# UCSD_QuadCopter_Rev1.net
KiCad netlist of a schematic drawn in EAGLE
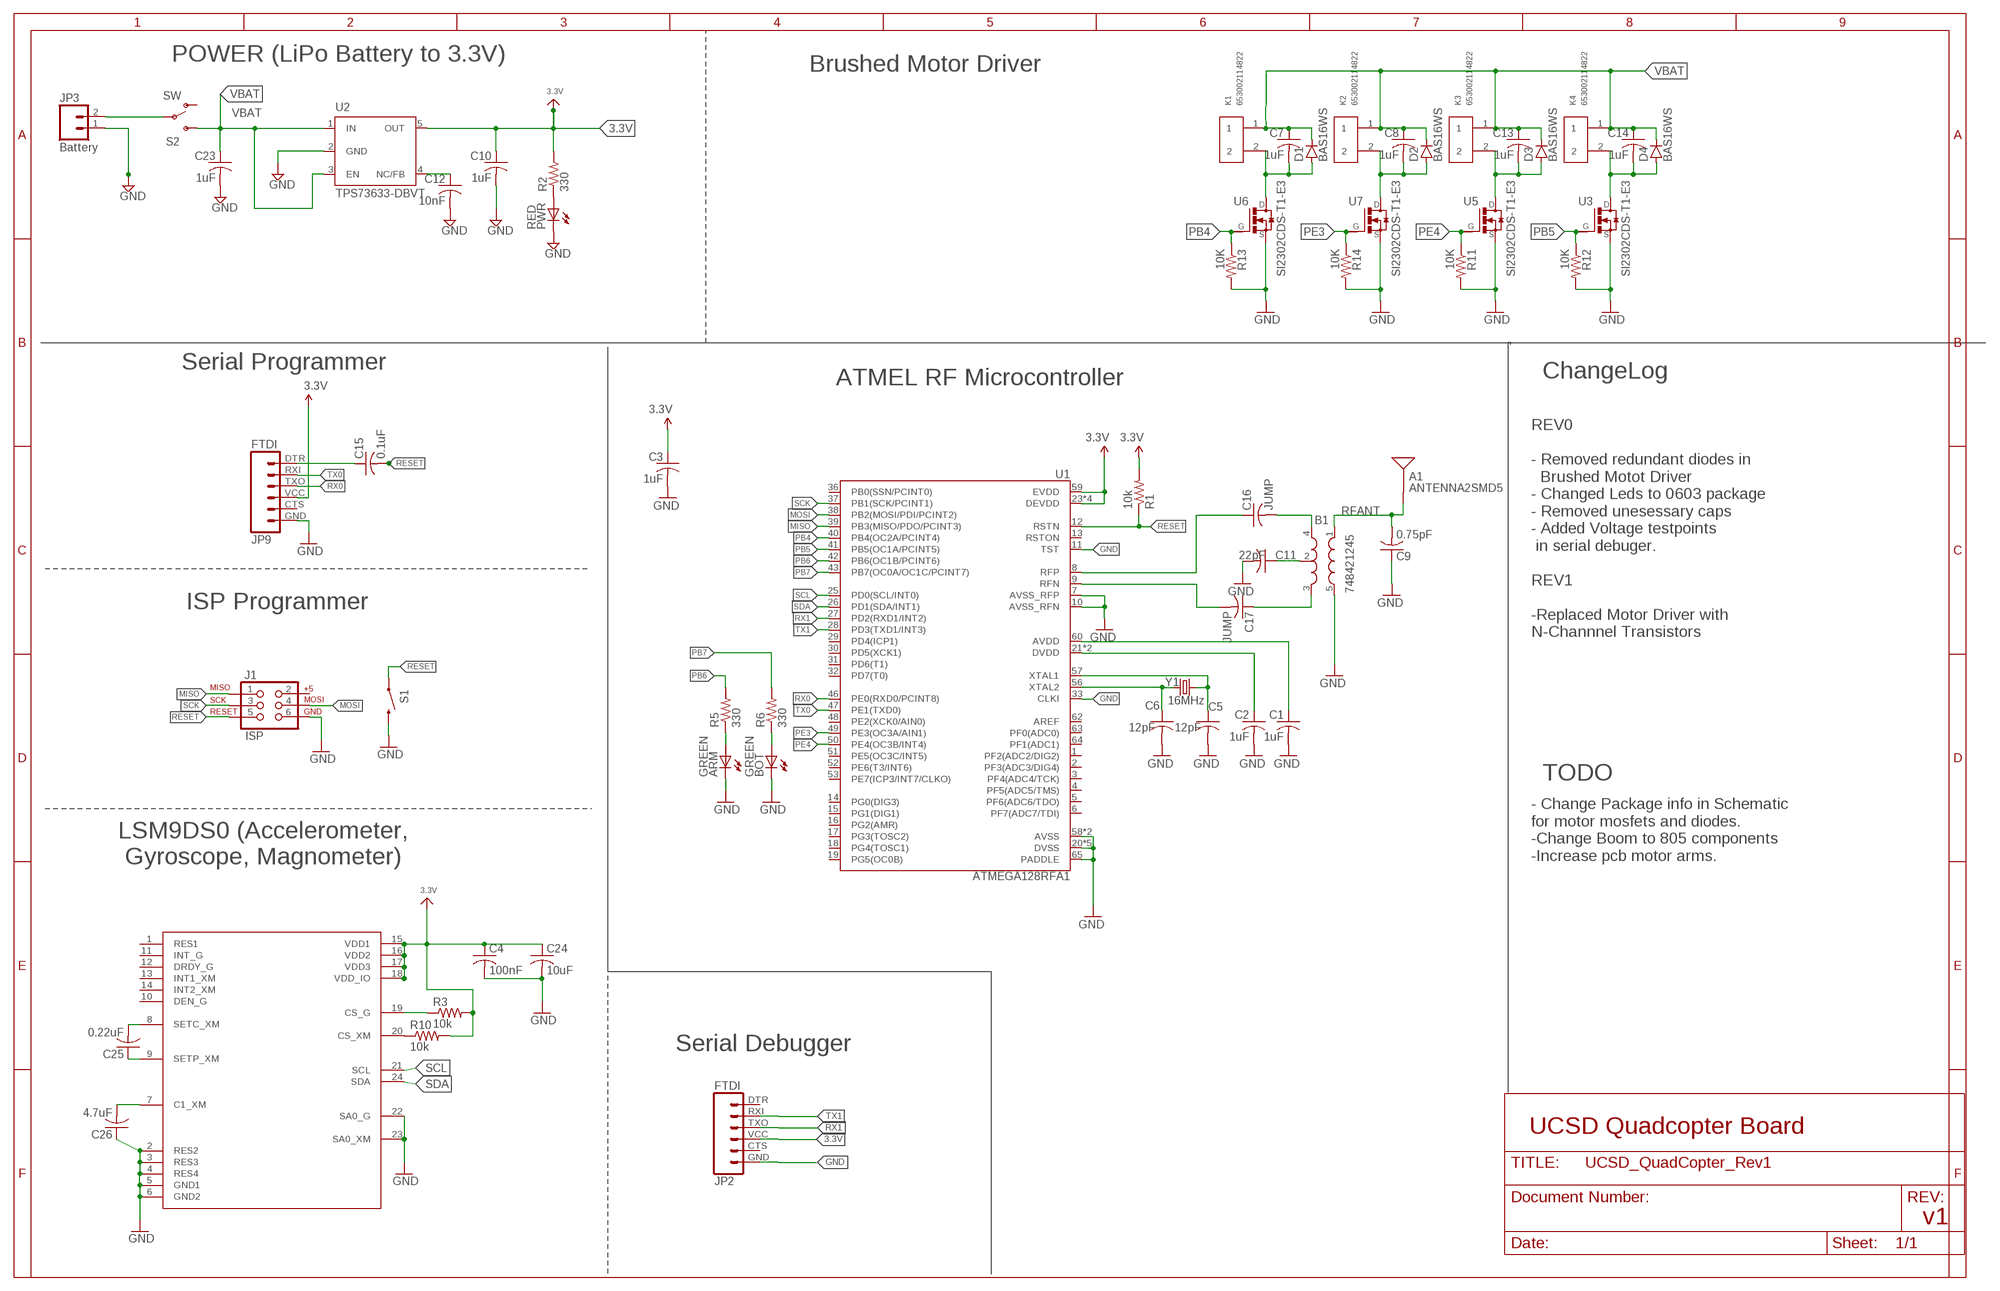
[diagram p0: schematic, sheet 1]

(export (version "E")
  (design (tool "Eeschema 10.0.6"))
  (components
    (comp (ref "A1")
      (value "ANTENNA2SMD5")
      (footprint "eagle-import:ANTENNA-CHIP5")
      (libsource (lib "eagle-import") (part "ANTENNA2SMD5"))
    )
    (comp (ref "ARM")
      (value "GREEN")
      (footprint "eagle-import:CHIP-LED0805")
      (libsource (lib "eagle-import") (part "LEDCHIP-LED0805"))
    )
    (comp (ref "B1")
      (value "748421245")
      (footprint "eagle-import:BALUN")
      (libsource (lib "eagle-import") (part "BALUN0805"))
    )
    (comp (ref "BOT")
      (value "GREEN")
      (footprint "eagle-import:CHIP-LED0805")
      (libsource (lib "eagle-import") (part "LEDCHIP-LED0805"))
    )
    (comp (ref "C1")
      (value "1uF")
      (footprint "eagle-import:C0805")
      (libsource (lib "eagle-import") (part "resistor_C-USC0805"))
    )
    (comp (ref "C2")
      (value "1uF")
      (footprint "eagle-import:C0805")
      (libsource (lib "eagle-import") (part "resistor_C-USC0805"))
    )
    (comp (ref "C3")
      (value "1uF")
      (footprint "eagle-import:C0805")
      (libsource (lib "eagle-import") (part "resistor_C-USC0805"))
    )
    (comp (ref "C4")
      (value "100nF")
      (footprint "eagle-import:C0805")
      (libsource (lib "eagle-import") (part "C-USC0805"))
    )
    (comp (ref "C5")
      (value "12pF")
      (footprint "eagle-import:C0805")
      (libsource (lib "eagle-import") (part "resistor_C-USC0805"))
    )
    (comp (ref "C6")
      (value "12pF")
      (footprint "eagle-import:C0805")
      (libsource (lib "eagle-import") (part "resistor_C-USC0805"))
    )
    (comp (ref "C7")
      (value "1uF")
      (footprint "eagle-import:C0805")
      (libsource (lib "eagle-import") (part "resistor_C-USC0805"))
    )
    (comp (ref "C8")
      (value "1uF")
      (footprint "eagle-import:C0805")
      (libsource (lib "eagle-import") (part "resistor_C-USC0805"))
    )
    (comp (ref "C9")
      (value "0.75pF")
      (footprint "eagle-import:C0805")
      (libsource (lib "eagle-import") (part "resistor_C-USC0805"))
    )
    (comp (ref "C10")
      (value "1uF")
      (footprint "eagle-import:C0805")
      (libsource (lib "eagle-import") (part "resistor_C-USC0805"))
    )
    (comp (ref "C11")
      (value "22pF")
      (footprint "eagle-import:C0805")
      (libsource (lib "eagle-import") (part "resistor_C-USC0805"))
    )
    (comp (ref "C12")
      (value "10nF")
      (footprint "eagle-import:C0805")
      (libsource (lib "eagle-import") (part "resistor_C-USC0805"))
    )
    (comp (ref "C13")
      (value "1uF")
      (footprint "eagle-import:C0805")
      (libsource (lib "eagle-import") (part "resistor_C-USC0805"))
    )
    (comp (ref "C14")
      (value "1uF")
      (footprint "eagle-import:C0805")
      (libsource (lib "eagle-import") (part "resistor_C-USC0805"))
    )
    (comp (ref "C15")
      (value "0.1uF")
      (footprint "eagle-import:C0805")
      (libsource (lib "eagle-import") (part "resistor_C-USC0805"))
    )
    (comp (ref "C16")
      (value "JUMP")
      (footprint "eagle-import:C0805")
      (libsource (lib "eagle-import") (part "resistor_C-USC0805"))
    )
    (comp (ref "C17")
      (value "JUMP")
      (footprint "eagle-import:C0805")
      (libsource (lib "eagle-import") (part "resistor_C-USC0805"))
    )
    (comp (ref "C23")
      (value "1uF")
      (footprint "eagle-import:C0805")
      (libsource (lib "eagle-import") (part "resistor_C-USC0805"))
    )
    (comp (ref "C24")
      (value "10uF")
      (footprint "eagle-import:C0805")
      (libsource (lib "eagle-import") (part "C-USC0805"))
    )
    (comp (ref "C25")
      (value "0.22uF")
      (footprint "eagle-import:C0805")
      (libsource (lib "eagle-import") (part "C-USC0805"))
    )
    (comp (ref "C26")
      (value "4.7uF")
      (footprint "eagle-import:C0805")
      (libsource (lib "eagle-import") (part "C-USC0805"))
    )
    (comp (ref "D1")
      (value "BAS16WS")
      (footprint "eagle-import:SOD323_ST")
      (libsource (lib "eagle-import") (part "BAS16WS"))
    )
    (comp (ref "D2")
      (value "BAS16WS")
      (footprint "eagle-import:SOD323_ST")
      (libsource (lib "eagle-import") (part "BAS16WS"))
    )
    (comp (ref "D3")
      (value "BAS16WS")
      (footprint "eagle-import:SOD323_ST")
      (libsource (lib "eagle-import") (part "BAS16WS"))
    )
    (comp (ref "D4")
      (value "BAS16WS")
      (footprint "eagle-import:SOD323_ST")
      (libsource (lib "eagle-import") (part "BAS16WS"))
    )
    (comp (ref "J1")
      (value "ISP")
      (footprint "eagle-import:2X3-NS")
      (libsource (lib "eagle-import") (part "AVR_SPI_PRG_6NS"))
    )
    (comp (ref "JP2")
      (value "FTDI")
      (footprint "eagle-import:FTDI_BASIC")
      (libsource (lib "eagle-import") (part "FTDI_BASICPTH"))
    )
    (comp (ref "JP3")
      (value "Battery")
      (footprint "eagle-import:1X02")
      (libsource (lib "eagle-import") (part "M02PTH"))
    )
    (comp (ref "JP9")
      (value "FTDI")
      (footprint "eagle-import:FTDI_BASIC")
      (libsource (lib "eagle-import") (part "FTDI_BASICPTH"))
    )
    (comp (ref "K1")
      (value "653002114822")
      (footprint "eagle-import:653002114822")
      (libsource (lib "eagle-import") (part "653002114822"))
    )
    (comp (ref "K2")
      (value "653002114822")
      (footprint "eagle-import:653002114822")
      (libsource (lib "eagle-import") (part "653002114822"))
    )
    (comp (ref "K3")
      (value "653002114822")
      (footprint "eagle-import:653002114822")
      (libsource (lib "eagle-import") (part "653002114822"))
    )
    (comp (ref "K4")
      (value "653002114822")
      (footprint "eagle-import:653002114822")
      (libsource (lib "eagle-import") (part "653002114822"))
    )
    (comp (ref "PWR")
      (value "RED")
      (footprint "eagle-import:CHIP-LED0805")
      (libsource (lib "eagle-import") (part "LEDCHIP-LED0805"))
    )
    (comp (ref "R1")
      (value "10k")
      (footprint "eagle-import:R0805")
      (libsource (lib "eagle-import") (part "R-US_R0805"))
    )
    (comp (ref "R2")
      (value "330")
      (footprint "eagle-import:R0805")
      (libsource (lib "eagle-import") (part "R-US_R0805"))
    )
    (comp (ref "R3")
      (value "10k")
      (footprint "eagle-import:R0805")
      (libsource (lib "eagle-import") (part "R-US_R0805"))
    )
    (comp (ref "R5")
      (value "330")
      (footprint "eagle-import:R0805")
      (libsource (lib "eagle-import") (part "R-US_R0805"))
    )
    (comp (ref "R6")
      (value "330")
      (footprint "eagle-import:R0805")
      (libsource (lib "eagle-import") (part "R-US_R0805"))
    )
    (comp (ref "R10")
      (value "10k")
      (footprint "eagle-import:R0805")
      (libsource (lib "eagle-import") (part "R-US_R0805"))
    )
    (comp (ref "R11")
      (value "10K")
      (footprint "eagle-import:R0805")
      (libsource (lib "eagle-import") (part "R-US_R0805"))
    )
    (comp (ref "R12")
      (value "10K")
      (footprint "eagle-import:R0805")
      (libsource (lib "eagle-import") (part "R-US_R0805"))
    )
    (comp (ref "R13")
      (value "10K")
      (footprint "eagle-import:R0805")
      (libsource (lib "eagle-import") (part "R-US_R0805"))
    )
    (comp (ref "R14")
      (value "10K")
      (footprint "eagle-import:R0805")
      (libsource (lib "eagle-import") (part "R-US_R0805"))
    )
    (comp (ref "S1")
      (value "SWITCH-MOMENTARY-2SMD")
      (footprint "eagle-import:TACTILE_SWITCH_SMD")
      (libsource (lib "eagle-import") (part "SWITCH-MOMENTARY-2SMD"))
    )
    (comp (ref "S2")
      (value "SW")
      (footprint "eagle-import:SWITCH-SPDT")
      (libsource (lib "eagle-import") (part "SWITCH-SPDTPTH"))
    )
    (comp (ref "U1")
      (value "ATMEGA128RFA1")
      (footprint "eagle-import:QFN-64")
      (libsource (lib "eagle-import") (part "ATMEGA128RFA1"))
    )
    (comp (ref "U2")
      (value "TPS73633-DBVT")
      (footprint "eagle-import:SOT23-DBV")
      (libsource (lib "eagle-import") (part "TPS73633-DBVT"))
    )
    (comp (ref "U3")
      (value "SI2302CDS-T1-E3")
      (footprint "eagle-import:SOT95P237X112-3N")
      (libsource (lib "eagle-import") (part "SI2302CDS-T1-E3"))
    )
    (comp (ref "U4")
      (value "LSM9DS0")
      (footprint "eagle-import:LGA-24")
      (libsource (lib "eagle-import") (part "LSM9DS0"))
    )
    (comp (ref "U5")
      (value "SI2302CDS-T1-E3")
      (footprint "eagle-import:SOT95P237X112-3N")
      (libsource (lib "eagle-import") (part "SI2302CDS-T1-E3"))
    )
    (comp (ref "U6")
      (value "SI2302CDS-T1-E3")
      (footprint "eagle-import:SOT95P237X112-3N")
      (libsource (lib "eagle-import") (part "SI2302CDS-T1-E3"))
    )
    (comp (ref "U7")
      (value "SI2302CDS-T1-E3")
      (footprint "eagle-import:SOT95P237X112-3N")
      (libsource (lib "eagle-import") (part "SI2302CDS-T1-E3"))
    )
    (comp (ref "Y1")
      (value "16MHz")
      (footprint "eagle-import:CRYSTAL-SMD-5X3")
      (libsource (lib "eagle-import") (part "CRYSTAL5X3"))
    )
  )
  (nets
    (net (code "1") (name "/RFANT") (class "Default")
      (node (ref "A1") (pin "FEED") (pinfunction "SIGNAL_FEED") (pintype "bidirectional"))
      (node (ref "B1") (pin "1") (pinfunction "IN_1") (pintype "bidirectional"))
      (node (ref "C9") (pin "2") (pinfunction "2_2") (pintype "passive"))
    )
    (net (code "2") (name "3.3V") (class "Default")
      (node (ref "C10") (pin "1") (pinfunction "1_1") (pintype "passive"))
      (node (ref "C24") (pin "1") (pinfunction "1_1") (pintype "passive"))
      (node (ref "C3") (pin "1") (pinfunction "1_1") (pintype "passive"))
      (node (ref "C4") (pin "1") (pinfunction "1_1") (pintype "passive"))
      (node (ref "JP2") (pin "VCC") (pinfunction "4_VCC") (pintype "passive"))
      (node (ref "JP9") (pin "VCC") (pinfunction "4_VCC") (pintype "passive"))
      (node (ref "R1") (pin "2") (pinfunction "2_2") (pintype "passive"))
      (node (ref "R10") (pin "2") (pinfunction "2_2") (pintype "passive"))
      (node (ref "R2") (pin "2") (pinfunction "2_2") (pintype "passive"))
      (node (ref "R3") (pin "2") (pinfunction "2_2") (pintype "passive"))
      (node (ref "U1") (pin "23") (pinfunction "DEVDD_23") (pintype "bidirectional"))
      (node (ref "U1") (pin "34") (pinfunction "DEVDD_34") (pintype "bidirectional"))
      (node (ref "U1") (pin "44") (pinfunction "DEVDD_44") (pintype "bidirectional"))
      (node (ref "U1") (pin "54") (pinfunction "DEVDD_54") (pintype "bidirectional"))
      (node (ref "U1") (pin "59") (pinfunction "EVDD_59") (pintype "bidirectional"))
      (node (ref "U2") (pin "5") (pinfunction "OUT_5") (pintype "passive"))
      (node (ref "U4") (pin "15") (pinfunction "VDD1_15") (pintype "bidirectional"))
      (node (ref "U4") (pin "16") (pinfunction "VDD2_16") (pintype "bidirectional"))
      (node (ref "U4") (pin "17") (pinfunction "VDD3_17") (pintype "bidirectional"))
      (node (ref "U4") (pin "18") (pinfunction "VDD_IO_18") (pintype "bidirectional"))
    )
    (net (code "3") (name "GND") (class "Default")
      (node (ref "ARM") (pin "C") (pinfunction "C_C") (pintype "passive"))
      (node (ref "B1") (pin "5") (pinfunction "GND_5") (pintype "bidirectional"))
      (node (ref "BOT") (pin "C") (pinfunction "C_C") (pintype "passive"))
      (node (ref "C1") (pin "2") (pinfunction "2_2") (pintype "passive"))
      (node (ref "C10") (pin "2") (pinfunction "2_2") (pintype "passive"))
      (node (ref "C11") (pin "2") (pinfunction "2_2") (pintype "passive"))
      (node (ref "C12") (pin "2") (pinfunction "2_2") (pintype "passive"))
      (node (ref "C2") (pin "2") (pinfunction "2_2") (pintype "passive"))
      (node (ref "C23") (pin "2") (pinfunction "2_2") (pintype "passive"))
      (node (ref "C24") (pin "2") (pinfunction "2_2") (pintype "passive"))
      (node (ref "C26") (pin "1") (pinfunction "1_1") (pintype "passive"))
      (node (ref "C3") (pin "2") (pinfunction "2_2") (pintype "passive"))
      (node (ref "C4") (pin "2") (pinfunction "2_2") (pintype "passive"))
      (node (ref "C5") (pin "2") (pinfunction "2_2") (pintype "passive"))
      (node (ref "C6") (pin "2") (pinfunction "2_2") (pintype "passive"))
      (node (ref "C9") (pin "1") (pinfunction "1_1") (pintype "passive"))
      (node (ref "J1") (pin "6") (pinfunction "6_6") (pintype "passive"))
      (node (ref "JP2") (pin "GND") (pinfunction "6_GND") (pintype "passive"))
      (node (ref "JP3") (pin "1") (pinfunction "1_1") (pintype "passive"))
      (node (ref "JP9") (pin "GND") (pinfunction "6_GND") (pintype "passive"))
      (node (ref "PWR") (pin "C") (pinfunction "C_C") (pintype "passive"))
      (node (ref "R11") (pin "2") (pinfunction "2_2") (pintype "passive"))
      (node (ref "R12") (pin "2") (pinfunction "2_2") (pintype "passive"))
      (node (ref "R13") (pin "2") (pinfunction "2_2") (pintype "passive"))
      (node (ref "R14") (pin "2") (pinfunction "2_2") (pintype "passive"))
      (node (ref "S1") (pin "3") (pinfunction "2_3") (pintype "passive"))
      (node (ref "U1") (pin "10") (pinfunction "AVSS_RFN_10") (pintype "bidirectional"))
      (node (ref "U1") (pin "11") (pinfunction "TST_11") (pintype "bidirectional"))
      (node (ref "U1") (pin "20") (pinfunction "DVSS_20") (pintype "bidirectional"))
      (node (ref "U1") (pin "24") (pinfunction "DVSS_24") (pintype "bidirectional"))
      (node (ref "U1") (pin "33") (pinfunction "CLKI_33") (pintype "bidirectional"))
      (node (ref "U1") (pin "35") (pinfunction "DVSS_35") (pintype "bidirectional"))
      (node (ref "U1") (pin "45") (pinfunction "DVSS_45") (pintype "bidirectional"))
      (node (ref "U1") (pin "55") (pinfunction "DVSS_55") (pintype "bidirectional"))
      (node (ref "U1") (pin "58") (pinfunction "AVSS_58") (pintype "bidirectional"))
      (node (ref "U1") (pin "61") (pinfunction "AVSS_61") (pintype "bidirectional"))
      (node (ref "U1") (pin "65") (pinfunction "PADDLE_65") (pintype "bidirectional"))
      (node (ref "U1") (pin "7") (pinfunction "AVSS_RFP_7") (pintype "bidirectional"))
      (node (ref "U2") (pin "2") (pinfunction "GND_2") (pintype "input"))
      (node (ref "U3") (pin "2") (pinfunction "S_2") (pintype "passive"))
      (node (ref "U4") (pin "2") (pinfunction "RES2_2") (pintype "bidirectional"))
      (node (ref "U4") (pin "22") (pinfunction "SA0_G_22") (pintype "bidirectional"))
      (node (ref "U4") (pin "23") (pinfunction "SA0_XM_23") (pintype "bidirectional"))
      (node (ref "U4") (pin "3") (pinfunction "RES3_3") (pintype "bidirectional"))
      (node (ref "U4") (pin "4") (pinfunction "RES4_4") (pintype "bidirectional"))
      (node (ref "U4") (pin "5") (pinfunction "GND1_5") (pintype "bidirectional"))
      (node (ref "U4") (pin "6") (pinfunction "GND2_6") (pintype "bidirectional"))
      (node (ref "U5") (pin "2") (pinfunction "S_2") (pintype "passive"))
      (node (ref "U6") (pin "2") (pinfunction "S_2") (pintype "passive"))
      (node (ref "U7") (pin "2") (pinfunction "S_2") (pintype "passive"))
    )
    (net (code "4") (name "MISO") (class "Default")
      (node (ref "J1") (pin "1") (pinfunction "1_1") (pintype "passive"))
      (node (ref "U1") (pin "39") (pinfunction "PB3(MISO/PDO/PCINT3)_39") (pintype "bidirectional"))
    )
    (net (code "5") (name "MOSI") (class "Default")
      (node (ref "J1") (pin "4") (pinfunction "4_4") (pintype "passive"))
      (node (ref "U1") (pin "38") (pinfunction "PB2(MOSI/PDI/PCINT2)_38") (pintype "bidirectional"))
    )
    (net (code "6") (name "Net-(ARM-PadA)") (class "Default")
      (node (ref "ARM") (pin "A") (pinfunction "A_A") (pintype "passive"))
      (node (ref "R5") (pin "1") (pinfunction "1_1") (pintype "passive"))
    )
    (net (code "7") (name "Net-(B1-GND-Pad2)") (class "Default")
      (node (ref "B1") (pin "2") (pinfunction "GND_2") (pintype "bidirectional"))
      (node (ref "C11") (pin "1") (pinfunction "1_1") (pintype "passive"))
    )
    (net (code "8") (name "Net-(B1-OUT1)") (class "Default")
      (node (ref "B1") (pin "4") (pinfunction "OUT1_4") (pintype "bidirectional"))
      (node (ref "C16") (pin "2") (pinfunction "2_2") (pintype "passive"))
    )
    (net (code "9") (name "Net-(B1-OUT2)") (class "Default")
      (node (ref "B1") (pin "3") (pinfunction "OUT2_3") (pintype "bidirectional"))
      (node (ref "C17") (pin "1") (pinfunction "1_1") (pintype "passive"))
    )
    (net (code "10") (name "Net-(BOT-PadA)") (class "Default")
      (node (ref "BOT") (pin "A") (pinfunction "A_A") (pintype "passive"))
      (node (ref "R6") (pin "1") (pinfunction "1_1") (pintype "passive"))
    )
    (net (code "11") (name "Net-(C2-Pad1)") (class "Default")
      (node (ref "C2") (pin "1") (pinfunction "1_1") (pintype "passive"))
      (node (ref "U1") (pin "21") (pinfunction "DVDD_21") (pintype "bidirectional"))
      (node (ref "U1") (pin "22") (pinfunction "DVDD_22") (pintype "bidirectional"))
    )
    (net (code "12") (name "Net-(JP9-1)") (class "Default")
      (node (ref "C15") (pin "1") (pinfunction "1_1") (pintype "passive"))
      (node (ref "JP9") (pin "DTR") (pinfunction "1_DTR") (pintype "passive"))
    )
    (net (code "13") (name "Net-(PWR-PadA)") (class "Default")
      (node (ref "PWR") (pin "A") (pinfunction "A_A") (pintype "passive"))
      (node (ref "R2") (pin "1") (pinfunction "1_1") (pintype "passive"))
    )
    (net (code "14") (name "Net-(S2-P)") (class "Default")
      (node (ref "JP3") (pin "2") (pinfunction "2_2") (pintype "passive"))
      (node (ref "S2") (pin "2") (pinfunction "P_2") (pintype "passive"))
    )
    (net (code "15") (name "Net-(U1-AVDD)") (class "Default")
      (node (ref "C1") (pin "1") (pinfunction "1_1") (pintype "passive"))
      (node (ref "U1") (pin "60") (pinfunction "AVDD_60") (pintype "bidirectional"))
    )
    (net (code "16") (name "Net-(U1-RFN)") (class "Default")
      (node (ref "C17") (pin "2") (pinfunction "2_2") (pintype "passive"))
      (node (ref "U1") (pin "9") (pinfunction "RFN_9") (pintype "bidirectional"))
    )
    (net (code "17") (name "Net-(U1-RFP)") (class "Default")
      (node (ref "C16") (pin "1") (pinfunction "1_1") (pintype "passive"))
      (node (ref "U1") (pin "8") (pinfunction "RFP_8") (pintype "bidirectional"))
    )
    (net (code "18") (name "Net-(U1-XTAL1)") (class "Default")
      (node (ref "C5") (pin "1") (pinfunction "1_1") (pintype "passive"))
      (node (ref "U1") (pin "57") (pinfunction "XTAL1_57") (pintype "bidirectional"))
      (node (ref "Y1") (pin "3") (pinfunction "2_3") (pintype "passive"))
    )
    (net (code "19") (name "Net-(U1-XTAL2)") (class "Default")
      (node (ref "C6") (pin "1") (pinfunction "1_1") (pintype "passive"))
      (node (ref "U1") (pin "56") (pinfunction "XTAL2_56") (pintype "bidirectional"))
      (node (ref "Y1") (pin "1") (pinfunction "1_1") (pintype "passive"))
    )
    (net (code "20") (name "Net-(U2-NC{slash}FB)") (class "Default")
      (node (ref "C12") (pin "1") (pinfunction "1_1") (pintype "passive"))
      (node (ref "U2") (pin "4") (pinfunction "NC/FB_4") (pintype "passive"))
    )
    (net (code "21") (name "Net-(U3-D)") (class "Default")
      (node (ref "C14") (pin "2") (pinfunction "2_2") (pintype "passive"))
      (node (ref "D4") (pin "A") (pinfunction "A_A") (pintype "passive"))
      (node (ref "K4") (pin "2") (pinfunction "2_2") (pintype "bidirectional"))
      (node (ref "U3") (pin "3") (pinfunction "D_3") (pintype "passive"))
    )
    (net (code "22") (name "Net-(U4-C1_XM)") (class "Default")
      (node (ref "C26") (pin "2") (pinfunction "2_2") (pintype "passive"))
      (node (ref "U4") (pin "7") (pinfunction "C1_XM_7") (pintype "bidirectional"))
    )
    (net (code "23") (name "Net-(U4-CS_G)") (class "Default")
      (node (ref "R3") (pin "1") (pinfunction "1_1") (pintype "passive"))
      (node (ref "U4") (pin "19") (pinfunction "CS_G_19") (pintype "bidirectional"))
    )
    (net (code "24") (name "Net-(U4-CS_XM)") (class "Default")
      (node (ref "R10") (pin "1") (pinfunction "1_1") (pintype "passive"))
      (node (ref "U4") (pin "20") (pinfunction "CS_XM_20") (pintype "bidirectional"))
    )
    (net (code "25") (name "Net-(U4-SETC_XM)") (class "Default")
      (node (ref "C25") (pin "2") (pinfunction "2_2") (pintype "passive"))
      (node (ref "U4") (pin "8") (pinfunction "SETC_XM_8") (pintype "bidirectional"))
    )
    (net (code "26") (name "Net-(U4-SETP_XM)") (class "Default")
      (node (ref "C25") (pin "1") (pinfunction "1_1") (pintype "passive"))
      (node (ref "U4") (pin "9") (pinfunction "SETP_XM_9") (pintype "bidirectional"))
    )
    (net (code "27") (name "Net-(U5-D)") (class "Default")
      (node (ref "C13") (pin "2") (pinfunction "2_2") (pintype "passive"))
      (node (ref "D3") (pin "A") (pinfunction "A_A") (pintype "passive"))
      (node (ref "K3") (pin "2") (pinfunction "2_2") (pintype "bidirectional"))
      (node (ref "U5") (pin "3") (pinfunction "D_3") (pintype "passive"))
    )
    (net (code "28") (name "Net-(U6-D)") (class "Default")
      (node (ref "C7") (pin "2") (pinfunction "2_2") (pintype "passive"))
      (node (ref "D1") (pin "A") (pinfunction "A_A") (pintype "passive"))
      (node (ref "K1") (pin "2") (pinfunction "2_2") (pintype "bidirectional"))
      (node (ref "U6") (pin "3") (pinfunction "D_3") (pintype "passive"))
    )
    (net (code "29") (name "Net-(U7-D)") (class "Default")
      (node (ref "C8") (pin "2") (pinfunction "2_2") (pintype "passive"))
      (node (ref "D2") (pin "A") (pinfunction "A_A") (pintype "passive"))
      (node (ref "K2") (pin "2") (pinfunction "2_2") (pintype "bidirectional"))
      (node (ref "U7") (pin "3") (pinfunction "D_3") (pintype "passive"))
    )
    (net (code "30") (name "PB4") (class "Default")
      (node (ref "R13") (pin "1") (pinfunction "1_1") (pintype "passive"))
      (node (ref "U1") (pin "40") (pinfunction "PB4(OC2A/PCINT4)_40") (pintype "bidirectional"))
      (node (ref "U6") (pin "1") (pinfunction "G_1") (pintype "passive"))
    )
    (net (code "31") (name "PB5") (class "Default")
      (node (ref "R12") (pin "1") (pinfunction "1_1") (pintype "passive"))
      (node (ref "U1") (pin "41") (pinfunction "PB5(OC1A/PCINT5)_41") (pintype "bidirectional"))
      (node (ref "U3") (pin "1") (pinfunction "G_1") (pintype "passive"))
    )
    (net (code "32") (name "PB6") (class "Default")
      (node (ref "R5") (pin "2") (pinfunction "2_2") (pintype "passive"))
      (node (ref "U1") (pin "42") (pinfunction "PB6(OC1B/PCINT6)_42") (pintype "bidirectional"))
    )
    (net (code "33") (name "PB7") (class "Default")
      (node (ref "R6") (pin "2") (pinfunction "2_2") (pintype "passive"))
      (node (ref "U1") (pin "43") (pinfunction "PB7(OC0A/OC1C/PCINT7)_43") (pintype "bidirectional"))
    )
    (net (code "34") (name "PE3") (class "Default")
      (node (ref "R14") (pin "1") (pinfunction "1_1") (pintype "passive"))
      (node (ref "U1") (pin "49") (pinfunction "PE3(OC3A/AIN1)_49") (pintype "bidirectional"))
      (node (ref "U7") (pin "1") (pinfunction "G_1") (pintype "passive"))
    )
    (net (code "35") (name "PE4") (class "Default")
      (node (ref "R11") (pin "1") (pinfunction "1_1") (pintype "passive"))
      (node (ref "U1") (pin "50") (pinfunction "PE4(OC3B/INT4)_50") (pintype "bidirectional"))
      (node (ref "U5") (pin "1") (pinfunction "G_1") (pintype "passive"))
    )
    (net (code "36") (name "RESET") (class "Default")
      (node (ref "C15") (pin "2") (pinfunction "2_2") (pintype "passive"))
      (node (ref "J1") (pin "5") (pinfunction "5_5") (pintype "passive"))
      (node (ref "R1") (pin "1") (pinfunction "1_1") (pintype "passive"))
      (node (ref "S1") (pin "1") (pinfunction "1_1") (pintype "passive"))
      (node (ref "U1") (pin "12") (pinfunction "RSTN_12") (pintype "bidirectional"))
    )
    (net (code "37") (name "RX0") (class "Default")
      (node (ref "JP9") (pin "TXO") (pinfunction "3_TXO") (pintype "passive"))
      (node (ref "U1") (pin "46") (pinfunction "PE0(RXD0/PCINT8)_46") (pintype "bidirectional"))
    )
    (net (code "38") (name "RX1") (class "Default")
      (node (ref "JP2") (pin "TXO") (pinfunction "3_TXO") (pintype "passive"))
      (node (ref "U1") (pin "27") (pinfunction "PD2(RXD1/INT2)_27") (pintype "bidirectional"))
    )
    (net (code "39") (name "SCK") (class "Default")
      (node (ref "J1") (pin "3") (pinfunction "3_3") (pintype "passive"))
      (node (ref "U1") (pin "37") (pinfunction "PB1(SCK/PCINT1)_37") (pintype "bidirectional"))
    )
    (net (code "40") (name "SCL") (class "Default")
      (node (ref "U1") (pin "25") (pinfunction "PD0(SCL/INT0)_25") (pintype "bidirectional"))
      (node (ref "U4") (pin "21") (pinfunction "SCL_21") (pintype "bidirectional"))
    )
    (net (code "41") (name "SDA") (class "Default")
      (node (ref "U1") (pin "26") (pinfunction "PD1(SDA/INT1)_26") (pintype "bidirectional"))
      (node (ref "U4") (pin "24") (pinfunction "SDA_24") (pintype "bidirectional"))
    )
    (net (code "42") (name "TX0") (class "Default")
      (node (ref "JP9") (pin "RXI") (pinfunction "2_RXI") (pintype "passive"))
      (node (ref "U1") (pin "47") (pinfunction "PE1(TXD0)_47") (pintype "bidirectional"))
    )
    (net (code "43") (name "TX1") (class "Default")
      (node (ref "JP2") (pin "RXI") (pinfunction "2_RXI") (pintype "passive"))
      (node (ref "U1") (pin "28") (pinfunction "PD3(TXD1/INT3)_28") (pintype "bidirectional"))
    )
    (net (code "44") (name "VBAT") (class "Default")
      (node (ref "C13") (pin "1") (pinfunction "1_1") (pintype "passive"))
      (node (ref "C14") (pin "1") (pinfunction "1_1") (pintype "passive"))
      (node (ref "C23") (pin "1") (pinfunction "1_1") (pintype "passive"))
      (node (ref "C7") (pin "1") (pinfunction "1_1") (pintype "passive"))
      (node (ref "C8") (pin "1") (pinfunction "1_1") (pintype "passive"))
      (node (ref "D1") (pin "C") (pinfunction "C_C") (pintype "passive"))
      (node (ref "D2") (pin "C") (pinfunction "C_C") (pintype "passive"))
      (node (ref "D3") (pin "C") (pinfunction "C_C") (pintype "passive"))
      (node (ref "D4") (pin "C") (pinfunction "C_C") (pintype "passive"))
      (node (ref "K1") (pin "1") (pinfunction "1_1") (pintype "bidirectional"))
      (node (ref "K2") (pin "1") (pinfunction "1_1") (pintype "bidirectional"))
      (node (ref "K3") (pin "1") (pinfunction "1_1") (pintype "bidirectional"))
      (node (ref "K4") (pin "1") (pinfunction "1_1") (pintype "bidirectional"))
      (node (ref "S2") (pin "3") (pinfunction "S_3") (pintype "passive"))
      (node (ref "U2") (pin "1") (pinfunction "IN_1") (pintype "input"))
      (node (ref "U2") (pin "3") (pinfunction "EN_3") (pintype "power_in"))
    )
    (net (code "45") (name "unconnected-(J1-Pad2)") (class "Default")
      (node (ref "J1") (pin "2") (pinfunction "2_2") (pintype "passive"))
    )
    (net (code "46") (name "unconnected-(JP2-1-PadDTR)") (class "Default")
      (node (ref "JP2") (pin "DTR") (pinfunction "1_DTR") (pintype "passive"))
    )
    (net (code "47") (name "unconnected-(JP2-5-PadCTS)") (class "Default")
      (node (ref "JP2") (pin "CTS") (pinfunction "5_CTS") (pintype "passive"))
    )
    (net (code "48") (name "unconnected-(JP9-5-PadCTS)") (class "Default")
      (node (ref "JP9") (pin "CTS") (pinfunction "5_CTS") (pintype "passive"))
    )
    (net (code "49") (name "unconnected-(S2-O-Pad1)") (class "Default")
      (node (ref "S2") (pin "1") (pinfunction "O_1") (pintype "passive"))
    )
    (net (code "50") (name "unconnected-(U1-AREF-Pad62)") (class "Default")
      (node (ref "U1") (pin "62") (pinfunction "AREF_62") (pintype "bidirectional"))
    )
    (net (code "51") (name "unconnected-(U1-PB0(SSN{slash}PCINT0)-Pad36)") (class "Default")
      (node (ref "U1") (pin "36") (pinfunction "PB0(SSN/PCINT0)_36") (pintype "bidirectional"))
    )
    (net (code "52") (name "unconnected-(U1-PD4(ICP1)-Pad29)") (class "Default")
      (node (ref "U1") (pin "29") (pinfunction "PD4(ICP1)_29") (pintype "bidirectional"))
    )
    (net (code "53") (name "unconnected-(U1-PD5(XCK1)-Pad30)") (class "Default")
      (node (ref "U1") (pin "30") (pinfunction "PD5(XCK1)_30") (pintype "bidirectional"))
    )
    (net (code "54") (name "unconnected-(U1-PD6(T1)-Pad31)") (class "Default")
      (node (ref "U1") (pin "31") (pinfunction "PD6(T1)_31") (pintype "bidirectional"))
    )
    (net (code "55") (name "unconnected-(U1-PD7(T0)-Pad32)") (class "Default")
      (node (ref "U1") (pin "32") (pinfunction "PD7(T0)_32") (pintype "bidirectional"))
    )
    (net (code "56") (name "unconnected-(U1-PE2(XCK0{slash}AIN0)-Pad48)") (class "Default")
      (node (ref "U1") (pin "48") (pinfunction "PE2(XCK0/AIN0)_48") (pintype "bidirectional"))
    )
    (net (code "57") (name "unconnected-(U1-PE5(OC3C{slash}INT5)-Pad51)") (class "Default")
      (node (ref "U1") (pin "51") (pinfunction "PE5(OC3C/INT5)_51") (pintype "bidirectional"))
    )
    (net (code "58") (name "unconnected-(U1-PE6(T3{slash}INT6)-Pad52)") (class "Default")
      (node (ref "U1") (pin "52") (pinfunction "PE6(T3/INT6)_52") (pintype "bidirectional"))
    )
    (net (code "59") (name "unconnected-(U1-PE7(ICP3{slash}INT7{slash}CLKO)-Pad53)") (class "Default")
      (node (ref "U1") (pin "53") (pinfunction "PE7(ICP3/INT7/CLKO)_53") (pintype "bidirectional"))
    )
    (net (code "60") (name "unconnected-(U1-PF0(ADC0)-Pad63)") (class "Default")
      (node (ref "U1") (pin "63") (pinfunction "PF0(ADC0)_63") (pintype "bidirectional"))
    )
    (net (code "61") (name "unconnected-(U1-PF1(ADC1)-Pad64)") (class "Default")
      (node (ref "U1") (pin "64") (pinfunction "PF1(ADC1)_64") (pintype "bidirectional"))
    )
    (net (code "62") (name "unconnected-(U1-PF2(ADC2{slash}DIG2)-Pad1)") (class "Default")
      (node (ref "U1") (pin "1") (pinfunction "PF2(ADC2/DIG2)_1") (pintype "bidirectional"))
    )
    (net (code "63") (name "unconnected-(U1-PF3(ADC3{slash}DIG4)-Pad2)") (class "Default")
      (node (ref "U1") (pin "2") (pinfunction "PF3(ADC3/DIG4)_2") (pintype "bidirectional"))
    )
    (net (code "64") (name "unconnected-(U1-PF4(ADC4{slash}TCK)-Pad3)") (class "Default")
      (node (ref "U1") (pin "3") (pinfunction "PF4(ADC4/TCK)_3") (pintype "bidirectional"))
    )
    (net (code "65") (name "unconnected-(U1-PF5(ADC5{slash}TMS)-Pad4)") (class "Default")
      (node (ref "U1") (pin "4") (pinfunction "PF5(ADC5/TMS)_4") (pintype "bidirectional"))
    )
    (net (code "66") (name "unconnected-(U1-PF6(ADC6{slash}TDO)-Pad5)") (class "Default")
      (node (ref "U1") (pin "5") (pinfunction "PF6(ADC6/TDO)_5") (pintype "bidirectional"))
    )
    (net (code "67") (name "unconnected-(U1-PF7(ADC7{slash}TDI)-Pad6)") (class "Default")
      (node (ref "U1") (pin "6") (pinfunction "PF7(ADC7/TDI)_6") (pintype "bidirectional"))
    )
    (net (code "68") (name "unconnected-(U1-PG0(DIG3)-Pad14)") (class "Default")
      (node (ref "U1") (pin "14") (pinfunction "PG0(DIG3)_14") (pintype "bidirectional"))
    )
    (net (code "69") (name "unconnected-(U1-PG1(DIG1)-Pad15)") (class "Default")
      (node (ref "U1") (pin "15") (pinfunction "PG1(DIG1)_15") (pintype "bidirectional"))
    )
    (net (code "70") (name "unconnected-(U1-PG2(AMR)-Pad16)") (class "Default")
      (node (ref "U1") (pin "16") (pinfunction "PG2(AMR)_16") (pintype "bidirectional"))
    )
    (net (code "71") (name "unconnected-(U1-PG3(TOSC2)-Pad17)") (class "Default")
      (node (ref "U1") (pin "17") (pinfunction "PG3(TOSC2)_17") (pintype "bidirectional"))
    )
    (net (code "72") (name "unconnected-(U1-PG4(TOSC1)-Pad18)") (class "Default")
      (node (ref "U1") (pin "18") (pinfunction "PG4(TOSC1)_18") (pintype "bidirectional"))
    )
    (net (code "73") (name "unconnected-(U1-PG5(OC0B)-Pad19)") (class "Default")
      (node (ref "U1") (pin "19") (pinfunction "PG5(OC0B)_19") (pintype "bidirectional"))
    )
    (net (code "74") (name "unconnected-(U1-RSTON-Pad13)") (class "Default")
      (node (ref "U1") (pin "13") (pinfunction "RSTON_13") (pintype "bidirectional"))
    )
    (net (code "75") (name "unconnected-(U4-DEN_G-Pad10)") (class "Default")
      (node (ref "U4") (pin "10") (pinfunction "DEN_G_10") (pintype "bidirectional"))
    )
    (net (code "76") (name "unconnected-(U4-DRDY_G-Pad12)") (class "Default")
      (node (ref "U4") (pin "12") (pinfunction "DRDY_G_12") (pintype "bidirectional"))
    )
    (net (code "77") (name "unconnected-(U4-INT1_XM-Pad13)") (class "Default")
      (node (ref "U4") (pin "13") (pinfunction "INT1_XM_13") (pintype "bidirectional"))
    )
    (net (code "78") (name "unconnected-(U4-INT2_XM-Pad14)") (class "Default")
      (node (ref "U4") (pin "14") (pinfunction "INT2_XM_14") (pintype "bidirectional"))
    )
    (net (code "79") (name "unconnected-(U4-INT_G-Pad11)") (class "Default")
      (node (ref "U4") (pin "11") (pinfunction "INT_G_11") (pintype "bidirectional"))
    )
    (net (code "80") (name "unconnected-(U4-RES1-Pad1)") (class "Default")
      (node (ref "U4") (pin "1") (pinfunction "RES1_1") (pintype "bidirectional"))
    )
  )
)
